# Hbridge.net
KiCad netlist of a schematic drawn in EAGLE
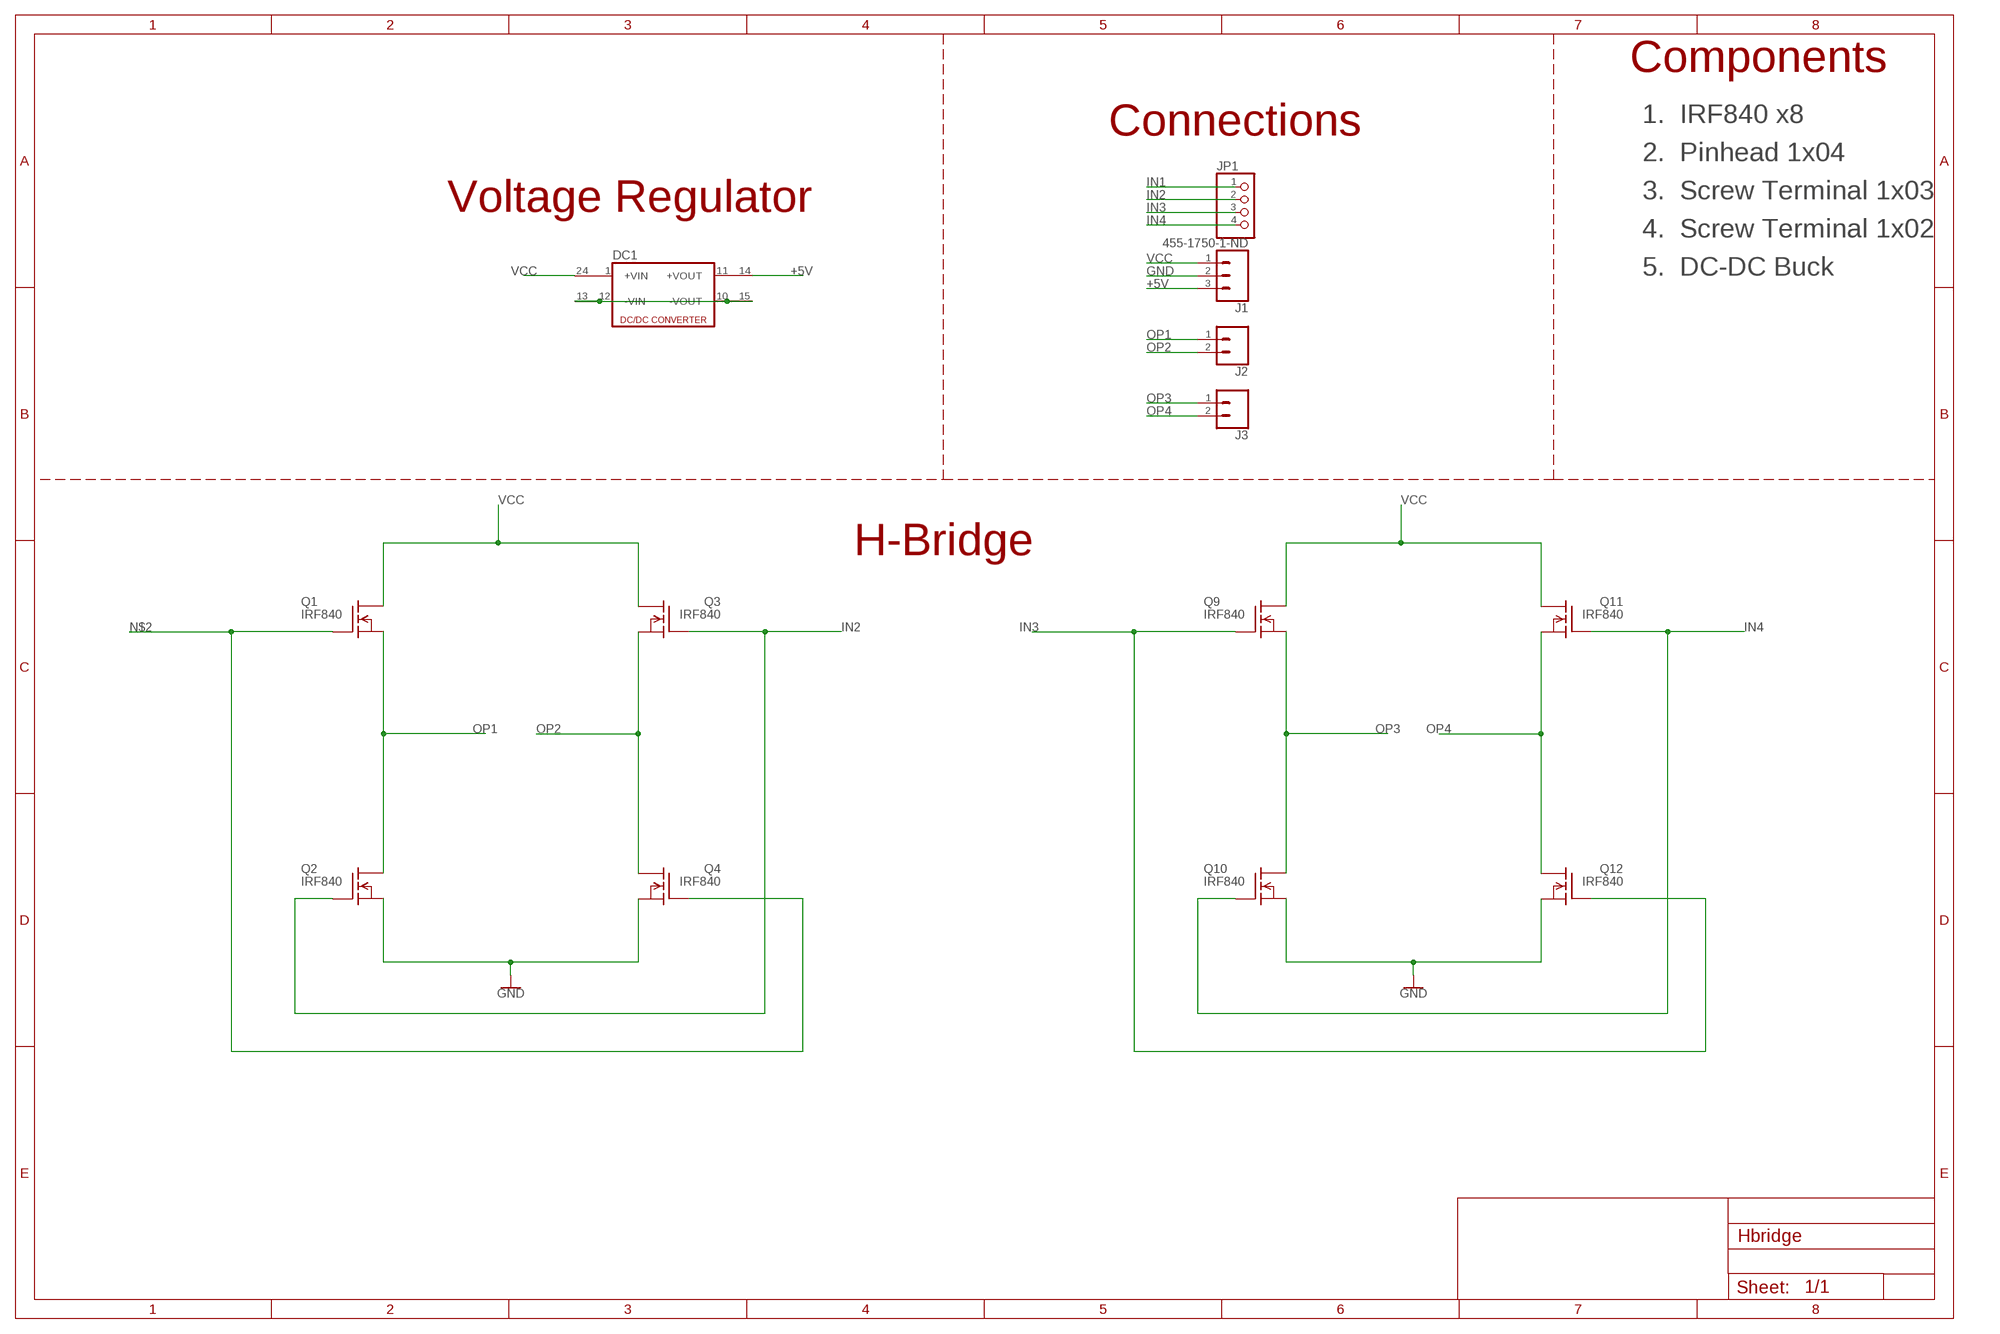
[diagram p0: schematic, sheet 1]

(export (version "E")
  (design (tool "Eeschema 10.0.6"))
  (components
    (comp (ref "DC1")
      (value "DC213R")
      (footprint "eagle-import:CMK")
      (libsource (lib "eagle-import") (part "DC213R"))
    )
    (comp (ref "J1")
      (value "455-1750-1-ND")
      (footprint "eagle-import:1X03")
      (libsource (lib "eagle-import") (part "CONN_03"))
    )
    (comp (ref "J2")
      (value "CONN_02")
      (footprint "eagle-import:1X02")
      (libsource (lib "eagle-import") (part "CONN_02"))
    )
    (comp (ref "J3")
      (value "CONN_02")
      (footprint "eagle-import:1X02")
      (libsource (lib "eagle-import") (part "CONN_02"))
    )
    (comp (ref "JP1")
      (value "PINHD-1X4")
      (footprint "eagle-import:1X04")
      (libsource (lib "eagle-import") (part "PINHD-1X4"))
    )
    (comp (ref "Q1")
      (value "IRF840")
      (footprint "eagle-import:TO220")
      (libsource (lib "eagle-import") (part "IRF840"))
    )
    (comp (ref "Q2")
      (value "IRF840")
      (footprint "eagle-import:TO220")
      (libsource (lib "eagle-import") (part "IRF840"))
    )
    (comp (ref "Q3")
      (value "IRF840")
      (footprint "eagle-import:TO220")
      (libsource (lib "eagle-import") (part "IRF840"))
    )
    (comp (ref "Q4")
      (value "IRF840")
      (footprint "eagle-import:TO220")
      (libsource (lib "eagle-import") (part "IRF840"))
    )
    (comp (ref "Q9")
      (value "IRF840")
      (footprint "eagle-import:TO220")
      (libsource (lib "eagle-import") (part "IRF840"))
    )
    (comp (ref "Q10")
      (value "IRF840")
      (footprint "eagle-import:TO220")
      (libsource (lib "eagle-import") (part "IRF840"))
    )
    (comp (ref "Q11")
      (value "IRF840")
      (footprint "eagle-import:TO220")
      (libsource (lib "eagle-import") (part "IRF840"))
    )
    (comp (ref "Q12")
      (value "IRF840")
      (footprint "eagle-import:TO220")
      (libsource (lib "eagle-import") (part "IRF840"))
    )
  )
  (nets
    (net (code "1") (name "/+5V") (class "Default")
      (node (ref "DC1") (pin "14") (pinfunction "+VOUT1_14") (pintype "passive"))
      (node (ref "J1") (pin "3") (pinfunction "3_3") (pintype "passive"))
    )
    (net (code "2") (name "/IN1") (class "Default")
      (node (ref "JP1") (pin "1") (pinfunction "1_1") (pintype "passive"))
    )
    (net (code "3") (name "/IN2") (class "Default")
      (node (ref "JP1") (pin "2") (pinfunction "2_2") (pintype "passive"))
      (node (ref "Q2") (pin "1") (pinfunction "G_1") (pintype "passive"))
      (node (ref "Q3") (pin "1") (pinfunction "G_1") (pintype "passive"))
    )
    (net (code "4") (name "/IN3") (class "Default")
      (node (ref "JP1") (pin "3") (pinfunction "3_3") (pintype "passive"))
      (node (ref "Q12") (pin "1") (pinfunction "G_1") (pintype "passive"))
      (node (ref "Q9") (pin "1") (pinfunction "G_1") (pintype "passive"))
    )
    (net (code "5") (name "/IN4") (class "Default")
      (node (ref "JP1") (pin "4") (pinfunction "4_4") (pintype "passive"))
      (node (ref "Q10") (pin "1") (pinfunction "G_1") (pintype "passive"))
      (node (ref "Q11") (pin "1") (pinfunction "G_1") (pintype "passive"))
    )
    (net (code "6") (name "/N$2") (class "Default")
      (node (ref "Q1") (pin "1") (pinfunction "G_1") (pintype "passive"))
      (node (ref "Q4") (pin "1") (pinfunction "G_1") (pintype "passive"))
    )
    (net (code "7") (name "/OP1") (class "Default")
      (node (ref "J2") (pin "1") (pinfunction "1_1") (pintype "passive"))
      (node (ref "Q1") (pin "3") (pinfunction "S_3") (pintype "passive"))
      (node (ref "Q2") (pin "2") (pinfunction "D_2") (pintype "passive"))
    )
    (net (code "8") (name "/OP2") (class "Default")
      (node (ref "J2") (pin "2") (pinfunction "2_2") (pintype "passive"))
      (node (ref "Q3") (pin "3") (pinfunction "S_3") (pintype "passive"))
      (node (ref "Q4") (pin "2") (pinfunction "D_2") (pintype "passive"))
    )
    (net (code "9") (name "/OP3") (class "Default")
      (node (ref "J3") (pin "1") (pinfunction "1_1") (pintype "passive"))
      (node (ref "Q10") (pin "2") (pinfunction "D_2") (pintype "passive"))
      (node (ref "Q9") (pin "3") (pinfunction "S_3") (pintype "passive"))
    )
    (net (code "10") (name "/OP4") (class "Default")
      (node (ref "J3") (pin "2") (pinfunction "2_2") (pintype "passive"))
      (node (ref "Q11") (pin "3") (pinfunction "S_3") (pintype "passive"))
      (node (ref "Q12") (pin "2") (pinfunction "D_2") (pintype "passive"))
    )
    (net (code "11") (name "/VCC") (class "Default")
      (node (ref "DC1") (pin "24") (pinfunction "+VIN1_24") (pintype "passive"))
      (node (ref "J1") (pin "1") (pinfunction "1_1") (pintype "passive"))
      (node (ref "Q1") (pin "2") (pinfunction "D_2") (pintype "passive"))
      (node (ref "Q11") (pin "2") (pinfunction "D_2") (pintype "passive"))
      (node (ref "Q3") (pin "2") (pinfunction "D_2") (pintype "passive"))
      (node (ref "Q9") (pin "2") (pinfunction "D_2") (pintype "passive"))
    )
    (net (code "12") (name "GND") (class "Default")
      (node (ref "J1") (pin "2") (pinfunction "2_2") (pintype "passive"))
      (node (ref "Q10") (pin "3") (pinfunction "S_3") (pintype "passive"))
      (node (ref "Q12") (pin "3") (pinfunction "S_3") (pintype "passive"))
      (node (ref "Q2") (pin "3") (pinfunction "S_3") (pintype "passive"))
      (node (ref "Q4") (pin "3") (pinfunction "S_3") (pintype "passive"))
    )
    (net (code "13") (name "Net-(DC1--VIN)") (class "Default")
      (node (ref "DC1") (pin "10") (pinfunction "-VOUT_10") (pintype "passive"))
      (node (ref "DC1") (pin "12") (pinfunction "-VIN_12") (pintype "passive"))
      (node (ref "DC1") (pin "13") (pinfunction "-VIN1_13") (pintype "passive"))
      (node (ref "DC1") (pin "15") (pinfunction "-VOUT1_15") (pintype "passive"))
    )
    (net (code "14") (name "unconnected-(DC1-+VIN-Pad1)") (class "Default")
      (node (ref "DC1") (pin "1") (pinfunction "+VIN_1") (pintype "passive"))
    )
    (net (code "15") (name "unconnected-(DC1-+VOUT-Pad11)") (class "Default")
      (node (ref "DC1") (pin "11") (pinfunction "+VOUT_11") (pintype "passive"))
    )
  )
)
